# solar_tester.net
KiCad netlist of a schematic drawn in EAGLE
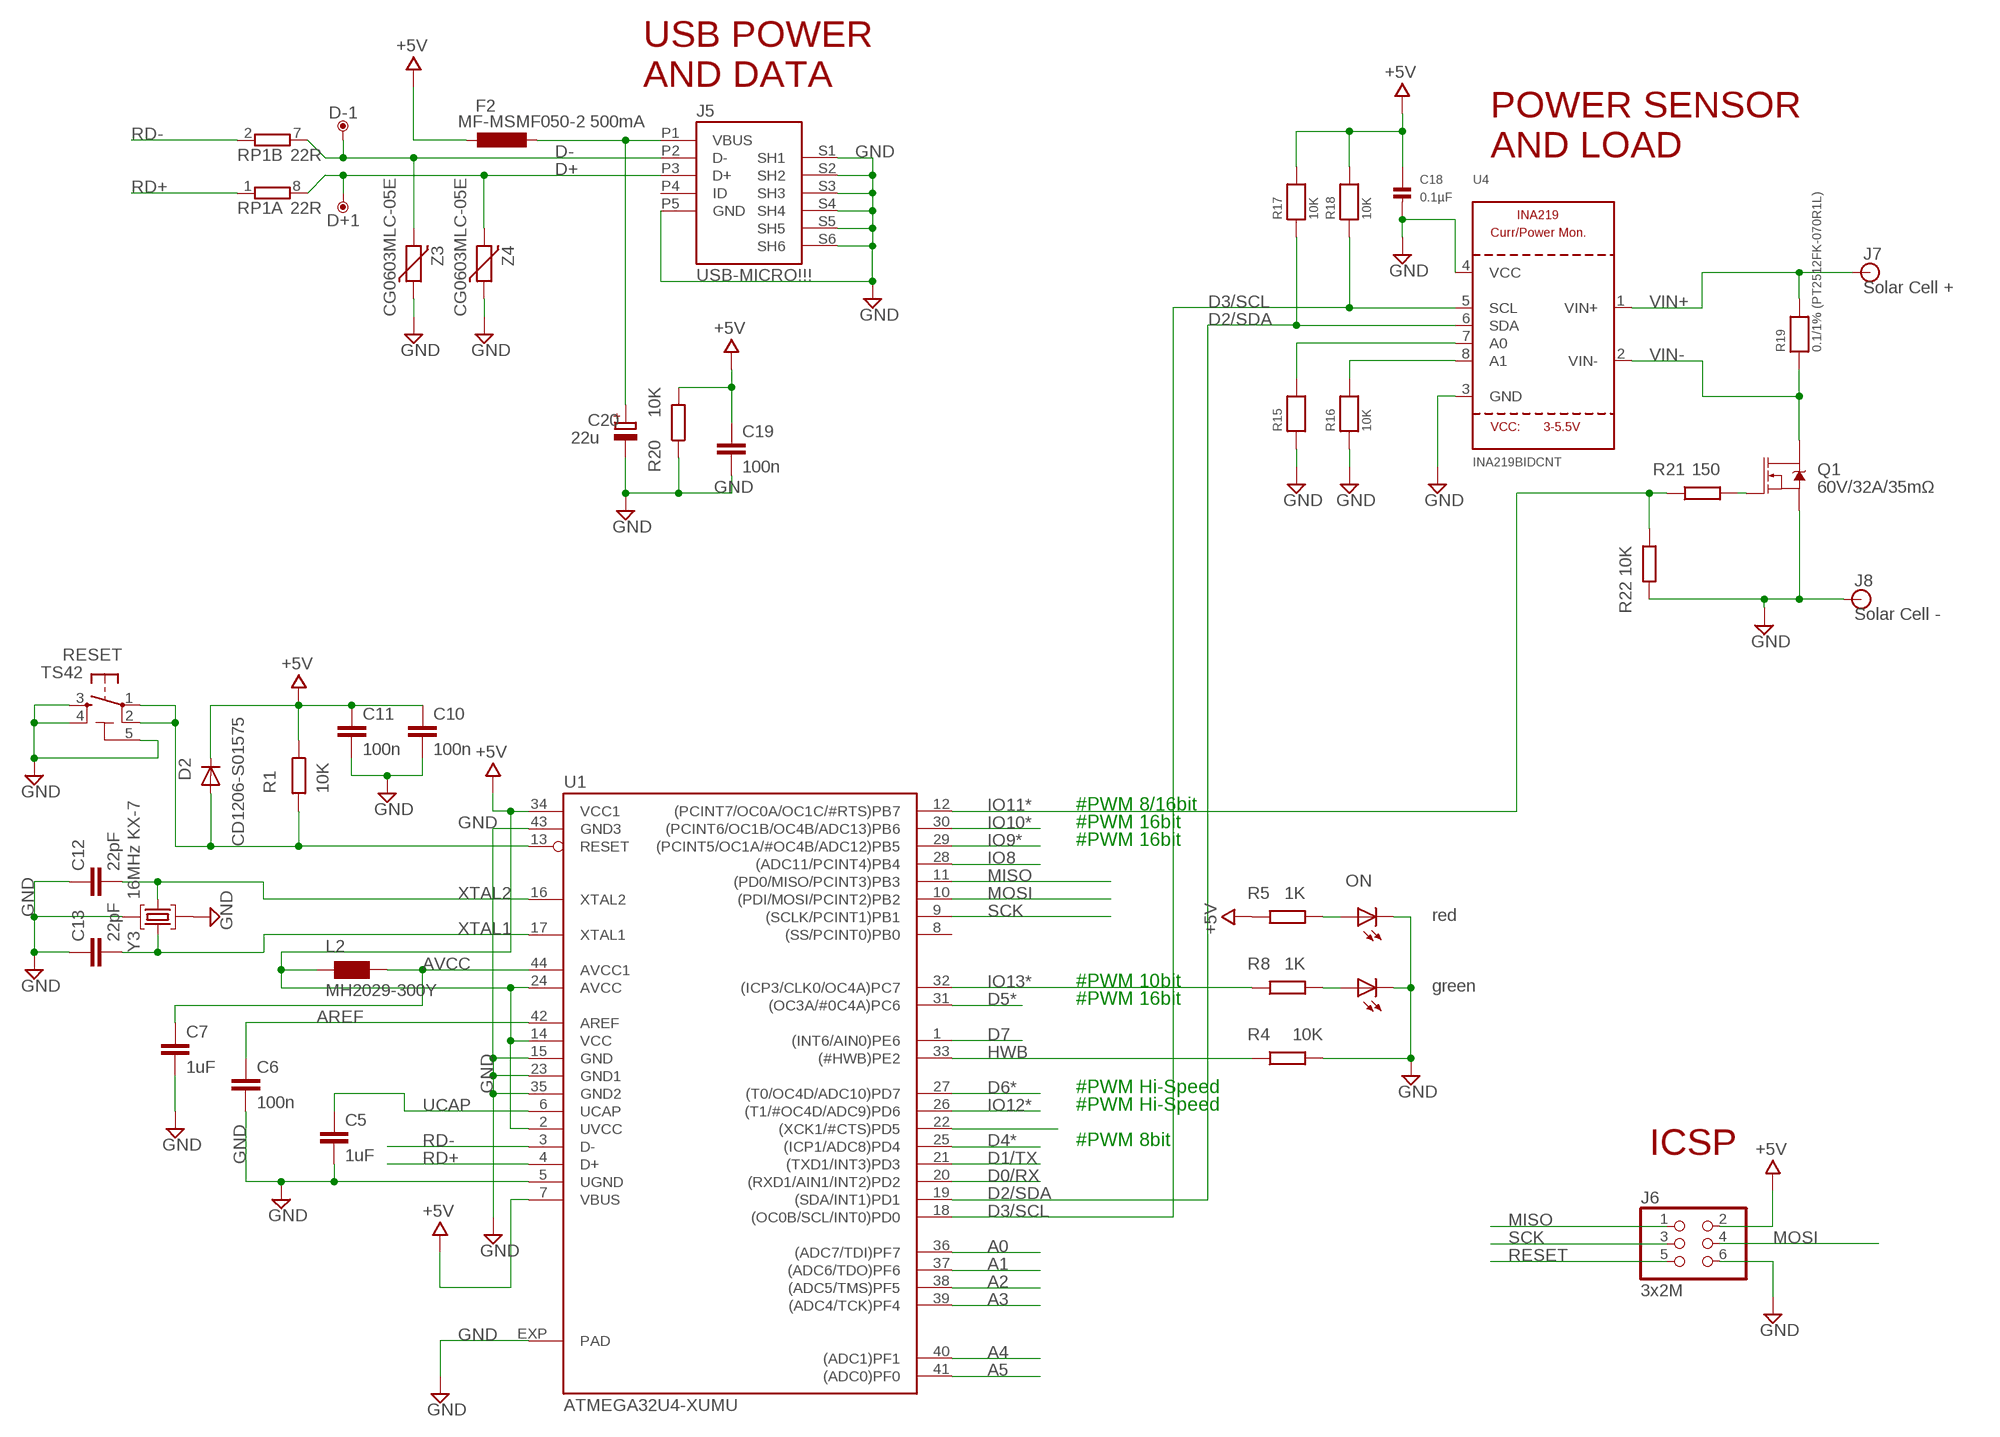
[diagram p0: schematic, sheet 1]

(export (version "E")
  (design (tool "Eeschema 10.0.6"))
  (components
    (comp (ref "C5")
      (value "1uF")
      (footprint "eagle-import:C0402")
      (libsource (lib "eagle-import") (part "C-EUC0402"))
    )
    (comp (ref "C6")
      (value "100n")
      (footprint "eagle-import:C0402")
      (libsource (lib "eagle-import") (part "C-EUC0402"))
    )
    (comp (ref "C7")
      (value "1uF")
      (footprint "eagle-import:C0402")
      (libsource (lib "eagle-import") (part "C-EUC0402"))
    )
    (comp (ref "C10")
      (value "100n")
      (footprint "eagle-import:C0402")
      (libsource (lib "eagle-import") (part "C-EUC0402"))
    )
    (comp (ref "C11")
      (value "100n")
      (footprint "eagle-import:C0402")
      (libsource (lib "eagle-import") (part "C-EUC0402"))
    )
    (comp (ref "C12")
      (value "22pF")
      (footprint "eagle-import:C0402")
      (libsource (lib "eagle-import") (part "C-EUC0402"))
    )
    (comp (ref "C13")
      (value "22pF")
      (footprint "eagle-import:C0402")
      (libsource (lib "eagle-import") (part "C-EUC0402"))
    )
    (comp (ref "C18")
      (value "0.1µF")
      (footprint "eagle-import:0805")
      (libsource (lib "eagle-import") (part "CAP_CERAMIC0805"))
    )
    (comp (ref "C19")
      (value "100n")
      (footprint "eagle-import:C0402")
      (libsource (lib "eagle-import") (part "C-EUC0402"))
    )
    (comp (ref "C20")
      (value "22u")
      (footprint "eagle-import:SMC_B")
      (libsource (lib "eagle-import") (part "CPOL-EUSMCB"))
    )
    (comp (ref "D+1")
      (value "DNP")
      (footprint "eagle-import:TP-1.00MM")
      (libsource (lib "eagle-import") (part "TPTP-1.00MM"))
    )
    (comp (ref "D-1")
      (value "DNP")
      (footprint "eagle-import:TP-1.00MM")
      (libsource (lib "eagle-import") (part "TPTP-1.00MM"))
    )
    (comp (ref "D2")
      (value "CD1206-S01575")
      (footprint "eagle-import:MINIMELF")
      (libsource (lib "eagle-import") (part "DIODE-MINIMELF"))
    )
    (comp (ref "F2")
      (value "MF-MSMF050-2 500mA")
      (footprint "eagle-import:L1812")
      (libsource (lib "eagle-import") (part "L-EUL1812"))
    )
    (comp (ref "J5")
      (value "USB-MICRO!!!")
      (footprint "eagle-import:CON2_USB_MICRO_B_AT")
      (libsource (lib "eagle-import") (part "MYCON2_USB-MINI-B"))
    )
    (comp (ref "J6")
      (value "3x2M")
      (footprint "eagle-import:2X03")
      (libsource (lib "eagle-import") (part "PINHD-2X3"))
    )
    (comp (ref "J7")
      (value "Solar Cell +")
      (footprint "eagle-import:BANANA_CONN")
      (libsource (lib "eagle-import") (part "BANANA_CONN"))
    )
    (comp (ref "J8")
      (value "Solar Cell -")
      (footprint "eagle-import:BANANA_CONN")
      (libsource (lib "eagle-import") (part "BANANA_CONN"))
    )
    (comp (ref "L")
      (value "green")
      (footprint "eagle-import:CHIPLED_0805")
      (libsource (lib "eagle-import") (part "LEDCHIPLED_0805"))
    )
    (comp (ref "L2")
      (value "MH2029-300Y")
      (footprint "eagle-import:0805")
      (libsource (lib "eagle-import") (part "WE-CBF_0805"))
    )
    (comp (ref "ON")
      (value "red")
      (footprint "eagle-import:CHIPLED_0805")
      (libsource (lib "eagle-import") (part "LEDCHIPLED_0805"))
    )
    (comp (ref "Q1")
      (value "60V/32A/35mΩ")
      (footprint "eagle-import:TO220V")
      (libsource (lib "eagle-import") (part "MOSFET-NCH-FQP30N06L"))
    )
    (comp (ref "R1")
      (value "10K")
      (footprint "eagle-import:R0402")
      (libsource (lib "eagle-import") (part "R-EU_R0402"))
    )
    (comp (ref "R4")
      (value "10K")
      (footprint "eagle-import:R0402")
      (libsource (lib "eagle-import") (part "R-EU_R0402"))
    )
    (comp (ref "R5")
      (value "1K")
      (footprint "eagle-import:R0402")
      (libsource (lib "eagle-import") (part "R-EU_R0402"))
    )
    (comp (ref "R8")
      (value "1K")
      (footprint "eagle-import:R0402")
      (libsource (lib "eagle-import") (part "R-EU_R0402"))
    )
    (comp (ref "R15")
      (value "10K")
      (footprint "eagle-import:0805")
      (libsource (lib "eagle-import") (part "RESISTOR0805"))
    )
    (comp (ref "R16")
      (value "10K")
      (footprint "eagle-import:0805")
      (libsource (lib "eagle-import") (part "RESISTOR0805"))
    )
    (comp (ref "R17")
      (value "10K")
      (footprint "eagle-import:0805")
      (libsource (lib "eagle-import") (part "RESISTOR0805"))
    )
    (comp (ref "R18")
      (value "10K")
      (footprint "eagle-import:0805")
      (libsource (lib "eagle-import") (part "RESISTOR0805"))
    )
    (comp (ref "R19")
      (value "0.1/1% (PT2512FK-070R1L)")
      (footprint "eagle-import:2512")
      (libsource (lib "eagle-import") (part "RESISTOR2512"))
    )
    (comp (ref "R20")
      (value "10K")
      (footprint "eagle-import:R0402")
      (libsource (lib "eagle-import") (part "R-EU_R0402"))
    )
    (comp (ref "R21")
      (value "150")
      (footprint "eagle-import:R0402")
      (libsource (lib "eagle-import") (part "R-EU_R0402"))
    )
    (comp (ref "R22")
      (value "10K")
      (footprint "eagle-import:R0402")
      (libsource (lib "eagle-import") (part "R-EU_R0402"))
    )
    (comp (ref "RESET")
      (value "TS42")
      (footprint "eagle-import:TS42")
      (libsource (lib "eagle-import") (part "TS42"))
    )
    (comp (ref "RP1")
      (value "22R")
      (footprint "eagle-import:CAY16")
      (libsource (lib "eagle-import") (part "4R-NCAY16"))
    )
    (comp (ref "U1")
      (value "ATMEGA32U4-XUMU")
      (footprint "eagle-import:QFN44ML7X7")
      (libsource (lib "eagle-import") (part "ATMEGA32U4-XUMU"))
    )
    (comp (ref "U4")
      (value "INA219BIDCNT")
      (footprint "eagle-import:SOT23-8")
      (libsource (lib "eagle-import") (part "INA219"))
    )
    (comp (ref "Y3")
      (value "16MHz KX-7")
      (footprint "eagle-import:CRYSTAL-3.2-2.5")
      (libsource (lib "eagle-import") (part "CRYSTAL-3.2-2.5"))
    )
    (comp (ref "Z3")
      (value "CG0603MLC-05E")
      (footprint "eagle-import:CT_CN0603")
      (libsource (lib "eagle-import") (part "VARISTORCN0603"))
    )
    (comp (ref "Z4")
      (value "CG0603MLC-05E")
      (footprint "eagle-import:CT_CN0603")
      (libsource (lib "eagle-import") (part "VARISTORCN0603"))
    )
  )
  (nets
    (net (code "1") (name "+5V") (class "Default")
      (node (ref "C10") (pin "1") (pinfunction "1_1") (pintype "passive"))
      (node (ref "C11") (pin "1") (pinfunction "1_1") (pintype "passive"))
      (node (ref "C18") (pin "1") (pinfunction "P$1_1") (pintype "passive"))
      (node (ref "C19") (pin "1") (pinfunction "1_1") (pintype "passive"))
      (node (ref "D2") (pin "C") (pinfunction "C_C") (pintype "passive"))
      (node (ref "F2") (pin "2") (pinfunction "2_2") (pintype "passive"))
      (node (ref "J6") (pin "2") (pinfunction "2_2") (pintype "passive"))
      (node (ref "L2") (pin "1") (pinfunction "1_1") (pintype "passive"))
      (node (ref "R1") (pin "1") (pinfunction "1_1") (pintype "passive"))
      (node (ref "R17") (pin "2") (pinfunction "2_2") (pintype "passive"))
      (node (ref "R18") (pin "2") (pinfunction "2_2") (pintype "passive"))
      (node (ref "R20") (pin "2") (pinfunction "2_2") (pintype "passive"))
      (node (ref "R5") (pin "1") (pinfunction "1_1") (pintype "passive"))
      (node (ref "U1") (pin "14") (pinfunction "VCC_14") (pintype "power_in"))
      (node (ref "U1") (pin "2") (pinfunction "UVCC_2") (pintype "power_in"))
      (node (ref "U1") (pin "24") (pinfunction "AVCC_24") (pintype "power_in"))
      (node (ref "U1") (pin "34") (pinfunction "VCC1_34") (pintype "power_in"))
      (node (ref "U1") (pin "7") (pinfunction "VBUS_7") (pintype "input"))
    )
    (net (code "2") (name "/A0") (class "Default")
      (node (ref "U1") (pin "36") (pinfunction "(ADC7/TDI)PF7_36") (pintype "bidirectional"))
    )
    (net (code "3") (name "/A1") (class "Default")
      (node (ref "U1") (pin "37") (pinfunction "(ADC6/TDO)PF6_37") (pintype "bidirectional"))
    )
    (net (code "4") (name "/A2") (class "Default")
      (node (ref "U1") (pin "38") (pinfunction "(ADC5/TMS)PF5_38") (pintype "bidirectional"))
    )
    (net (code "5") (name "/A3") (class "Default")
      (node (ref "U1") (pin "39") (pinfunction "(ADC4/TCK)PF4_39") (pintype "bidirectional"))
    )
    (net (code "6") (name "/A4") (class "Default")
      (node (ref "U1") (pin "40") (pinfunction "(ADC1)PF1_40") (pintype "bidirectional"))
    )
    (net (code "7") (name "/A5") (class "Default")
      (node (ref "U1") (pin "41") (pinfunction "(ADC0)PF0_41") (pintype "bidirectional"))
    )
    (net (code "8") (name "/AREF") (class "Default")
      (node (ref "C6") (pin "1") (pinfunction "1_1") (pintype "passive"))
      (node (ref "U1") (pin "42") (pinfunction "AREF_42") (pintype "power_in"))
    )
    (net (code "9") (name "/AVCC") (class "Default")
      (node (ref "C7") (pin "1") (pinfunction "1_1") (pintype "passive"))
      (node (ref "L2") (pin "2") (pinfunction "2_2") (pintype "passive"))
      (node (ref "U1") (pin "44") (pinfunction "AVCC1_44") (pintype "power_in"))
    )
    (net (code "10") (name "/D+") (class "Default")
      (node (ref "D+1") (pin "X") (pinfunction "P$1_X") (pintype "passive"))
      (node (ref "J5") (pin "P3") (pinfunction "D+_P3") (pintype "bidirectional"))
      (node (ref "RP1") (pin "8") (pinfunction "2_8") (pintype "passive"))
      (node (ref "Z4") (pin "2") (pinfunction "2_2") (pintype "passive"))
    )
    (net (code "11") (name "/D-") (class "Default")
      (node (ref "D-1") (pin "X") (pinfunction "P$1_X") (pintype "passive"))
      (node (ref "J5") (pin "P2") (pinfunction "D-_P2") (pintype "bidirectional"))
      (node (ref "RP1") (pin "7") (pinfunction "2_7") (pintype "passive"))
      (node (ref "Z3") (pin "2") (pinfunction "2_2") (pintype "passive"))
    )
    (net (code "12") (name "/D0{slash}RX") (class "Default")
      (node (ref "U1") (pin "20") (pinfunction "(RXD1/AIN1/INT2)PD2_20") (pintype "bidirectional"))
    )
    (net (code "13") (name "/D1{slash}TX") (class "Default")
      (node (ref "U1") (pin "21") (pinfunction "(TXD1/INT3)PD3_21") (pintype "bidirectional"))
    )
    (net (code "14") (name "/D2{slash}SDA") (class "Default")
      (node (ref "R17") (pin "1") (pinfunction "1_1") (pintype "passive"))
      (node (ref "U1") (pin "19") (pinfunction "(SDA/INT1)PD1_19") (pintype "bidirectional"))
      (node (ref "U4") (pin "6") (pinfunction "SDA_6") (pintype "bidirectional"))
    )
    (net (code "15") (name "/D3{slash}SCL") (class "Default")
      (node (ref "R18") (pin "1") (pinfunction "1_1") (pintype "passive"))
      (node (ref "U1") (pin "18") (pinfunction "(OC0B/SCL/INT0)PD0_18") (pintype "bidirectional"))
      (node (ref "U4") (pin "5") (pinfunction "SCL_5") (pintype "bidirectional"))
    )
    (net (code "16") (name "/D4*") (class "Default")
      (node (ref "U1") (pin "25") (pinfunction "(ICP1/ADC8)PD4_25") (pintype "bidirectional"))
    )
    (net (code "17") (name "/D5*") (class "Default")
      (node (ref "U1") (pin "31") (pinfunction "(OC3A/#0C4A)PC6_31") (pintype "bidirectional"))
    )
    (net (code "18") (name "/D6*") (class "Default")
      (node (ref "U1") (pin "27") (pinfunction "(T0/OC4D/ADC10)PD7_27") (pintype "bidirectional"))
    )
    (net (code "19") (name "/D7") (class "Default")
      (node (ref "U1") (pin "1") (pinfunction "(INT6/AIN0)PE6_1") (pintype "bidirectional"))
    )
    (net (code "20") (name "/HWB") (class "Default")
      (node (ref "R4") (pin "1") (pinfunction "1_1") (pintype "passive"))
      (node (ref "U1") (pin "33") (pinfunction "(#HWB)PE2_33") (pintype "bidirectional"))
    )
    (net (code "21") (name "/IO8") (class "Default")
      (node (ref "U1") (pin "28") (pinfunction "(ADC11/PCINT4)PB4_28") (pintype "bidirectional"))
    )
    (net (code "22") (name "/IO9*") (class "Default")
      (node (ref "U1") (pin "29") (pinfunction "(PCINT5/OC1A/#OC4B/ADC12)PB5_29") (pintype "bidirectional"))
    )
    (net (code "23") (name "/IO10*") (class "Default")
      (node (ref "U1") (pin "30") (pinfunction "(PCINT6/OC1B/OC4B/ADC13)PB6_30") (pintype "bidirectional"))
    )
    (net (code "24") (name "/IO11*") (class "Default")
      (node (ref "R21") (pin "1") (pinfunction "1_1") (pintype "passive"))
      (node (ref "R22") (pin "2") (pinfunction "2_2") (pintype "passive"))
      (node (ref "U1") (pin "12") (pinfunction "(PCINT7/OC0A/OC1C/#RTS)PB7_12") (pintype "bidirectional"))
    )
    (net (code "25") (name "/IO12*") (class "Default")
      (node (ref "U1") (pin "26") (pinfunction "(T1/#OC4D/ADC9)PD6_26") (pintype "bidirectional"))
    )
    (net (code "26") (name "/IO13*") (class "Default")
      (node (ref "R8") (pin "1") (pinfunction "1_1") (pintype "passive"))
      (node (ref "U1") (pin "32") (pinfunction "(ICP3/CLK0/OC4A)PC7_32") (pintype "bidirectional"))
    )
    (net (code "27") (name "/MISO") (class "Default")
      (node (ref "J6") (pin "1") (pinfunction "1_1") (pintype "passive"))
      (node (ref "U1") (pin "11") (pinfunction "(PD0/MISO/PCINT3)PB3_11") (pintype "bidirectional"))
    )
    (net (code "28") (name "/MOSI") (class "Default")
      (node (ref "J6") (pin "4") (pinfunction "4_4") (pintype "passive"))
      (node (ref "U1") (pin "10") (pinfunction "(PDI/MOSI/PCINT2)PB2_10") (pintype "bidirectional"))
    )
    (net (code "29") (name "/RD+") (class "Default")
      (node (ref "RP1") (pin "1") (pinfunction "1_1") (pintype "passive"))
      (node (ref "U1") (pin "4") (pinfunction "D+_4") (pintype "bidirectional"))
    )
    (net (code "30") (name "/RD-") (class "Default")
      (node (ref "RP1") (pin "2") (pinfunction "1_2") (pintype "passive"))
      (node (ref "U1") (pin "3") (pinfunction "D-_3") (pintype "bidirectional"))
    )
    (net (code "31") (name "/RESET") (class "Default")
      (node (ref "J6") (pin "5") (pinfunction "5_5") (pintype "passive"))
    )
    (net (code "32") (name "/SCK") (class "Default")
      (node (ref "J6") (pin "3") (pinfunction "3_3") (pintype "passive"))
      (node (ref "U1") (pin "9") (pinfunction "(SCLK/PCINT1)PB1_9") (pintype "bidirectional"))
    )
    (net (code "33") (name "/UCAP") (class "Default")
      (node (ref "C5") (pin "1") (pinfunction "1_1") (pintype "passive"))
      (node (ref "U1") (pin "6") (pinfunction "UCAP_6") (pintype "passive"))
    )
    (net (code "34") (name "/VIN+") (class "Default")
      (node (ref "J7") (pin "P$1") (pinfunction "1_P$1") (pintype "passive"))
      (node (ref "R19") (pin "2") (pinfunction "2_2") (pintype "passive"))
      (node (ref "U4") (pin "1") (pinfunction "VIN+_1") (pintype "bidirectional"))
    )
    (net (code "35") (name "/VIN-") (class "Default")
      (node (ref "Q1") (pin "2") (pinfunction "D_2") (pintype "bidirectional"))
      (node (ref "R19") (pin "1") (pinfunction "1_1") (pintype "passive"))
      (node (ref "U4") (pin "2") (pinfunction "VIN-_2") (pintype "bidirectional"))
    )
    (net (code "36") (name "/XTAL1") (class "Default")
      (node (ref "C13") (pin "2") (pinfunction "2_2") (pintype "passive"))
      (node (ref "U1") (pin "17") (pinfunction "XTAL1_17") (pintype "bidirectional"))
      (node (ref "Y3") (pin "3") (pinfunction "C2_3") (pintype "passive"))
    )
    (net (code "37") (name "/XTAL2") (class "Default")
      (node (ref "C12") (pin "2") (pinfunction "2_2") (pintype "passive"))
      (node (ref "U1") (pin "16") (pinfunction "XTAL2_16") (pintype "bidirectional"))
      (node (ref "Y3") (pin "1") (pinfunction "C1_1") (pintype "passive"))
    )
    (net (code "38") (name "GND") (class "Default")
      (node (ref "C10") (pin "2") (pinfunction "2_2") (pintype "passive"))
      (node (ref "C11") (pin "2") (pinfunction "2_2") (pintype "passive"))
      (node (ref "C12") (pin "1") (pinfunction "1_1") (pintype "passive"))
      (node (ref "C13") (pin "1") (pinfunction "1_1") (pintype "passive"))
      (node (ref "C18") (pin "2") (pinfunction "P$2_2") (pintype "passive"))
      (node (ref "C19") (pin "2") (pinfunction "2_2") (pintype "passive"))
      (node (ref "C20") (pin "-") (pinfunction "-_-") (pintype "passive"))
      (node (ref "C5") (pin "2") (pinfunction "2_2") (pintype "passive"))
      (node (ref "C6") (pin "2") (pinfunction "2_2") (pintype "passive"))
      (node (ref "C7") (pin "2") (pinfunction "2_2") (pintype "passive"))
      (node (ref "J5") (pin "P5") (pinfunction "GND_P5") (pintype "passive"))
      (node (ref "J5") (pin "S1") (pinfunction "SH1_S1") (pintype "passive"))
      (node (ref "J5") (pin "S2") (pinfunction "SH2_S2") (pintype "passive"))
      (node (ref "J5") (pin "S3") (pinfunction "SH3_S3") (pintype "passive"))
      (node (ref "J5") (pin "S4") (pinfunction "SH4_S4") (pintype "passive"))
      (node (ref "J5") (pin "S5") (pinfunction "SH5_S5") (pintype "passive"))
      (node (ref "J5") (pin "S6") (pinfunction "SH6_S6") (pintype "passive"))
      (node (ref "J6") (pin "6") (pinfunction "6_6") (pintype "passive"))
      (node (ref "J8") (pin "P$1") (pinfunction "1_P$1") (pintype "passive"))
      (node (ref "L") (pin "C") (pinfunction "C_C") (pintype "passive"))
      (node (ref "ON") (pin "C") (pinfunction "C_C") (pintype "passive"))
      (node (ref "Q1") (pin "3") (pinfunction "S_3") (pintype "bidirectional"))
      (node (ref "R15") (pin "1") (pinfunction "1_1") (pintype "passive"))
      (node (ref "R16") (pin "1") (pinfunction "1_1") (pintype "passive"))
      (node (ref "R20") (pin "1") (pinfunction "1_1") (pintype "passive"))
      (node (ref "R22") (pin "1") (pinfunction "1_1") (pintype "passive"))
      (node (ref "R4") (pin "2") (pinfunction "2_2") (pintype "passive"))
      (node (ref "RESET") (pin "3") (pinfunction "3_3") (pintype "passive"))
      (node (ref "RESET") (pin "4") (pinfunction "4_4") (pintype "passive"))
      (node (ref "RESET") (pin "5") (pinfunction "5-GND_5") (pintype "power_in"))
      (node (ref "U1") (pin "15") (pinfunction "GND_15") (pintype "power_in"))
      (node (ref "U1") (pin "23") (pinfunction "GND1_23") (pintype "power_in"))
      (node (ref "U1") (pin "35") (pinfunction "GND2_35") (pintype "power_in"))
      (node (ref "U1") (pin "43") (pinfunction "GND3_43") (pintype "power_in"))
      (node (ref "U1") (pin "5") (pinfunction "UGND_5") (pintype "power_in"))
      (node (ref "U1") (pin "EXP") (pinfunction "PAD_EXP") (pintype "power_in"))
      (node (ref "U4") (pin "3") (pinfunction "GND_3") (pintype "bidirectional"))
      (node (ref "U4") (pin "4") (pinfunction "VCC_4") (pintype "bidirectional"))
      (node (ref "Y3") (pin "2") (pinfunction "GND_2") (pintype "passive"))
      (node (ref "Y3") (pin "4") (pinfunction "GND_4") (pintype "passive"))
      (node (ref "Z3") (pin "1") (pinfunction "1_1") (pintype "passive"))
      (node (ref "Z4") (pin "1") (pinfunction "1_1") (pintype "passive"))
    )
    (net (code "39") (name "Net-(J5-VBUS)") (class "Default")
      (node (ref "C20") (pin "+") (pinfunction "+_+") (pintype "passive"))
      (node (ref "F2") (pin "1") (pinfunction "1_1") (pintype "passive"))
      (node (ref "J5") (pin "P1") (pinfunction "VBUS_P1") (pintype "power_in"))
    )
    (net (code "40") (name "Net-(L-PadA)") (class "Default")
      (node (ref "L") (pin "A") (pinfunction "A_A") (pintype "passive"))
      (node (ref "R8") (pin "2") (pinfunction "2_2") (pintype "passive"))
    )
    (net (code "41") (name "Net-(ON-PadA)") (class "Default")
      (node (ref "ON") (pin "A") (pinfunction "A_A") (pintype "passive"))
      (node (ref "R5") (pin "2") (pinfunction "2_2") (pintype "passive"))
    )
    (net (code "42") (name "Net-(Q1-G)") (class "Default")
      (node (ref "Q1") (pin "1") (pinfunction "G_1") (pintype "bidirectional"))
      (node (ref "R21") (pin "2") (pinfunction "2_2") (pintype "passive"))
    )
    (net (code "43") (name "Net-(U1-RESET)") (class "Default")
      (node (ref "D2") (pin "A") (pinfunction "A_A") (pintype "passive"))
      (node (ref "R1") (pin "2") (pinfunction "2_2") (pintype "passive"))
      (node (ref "RESET") (pin "1") (pinfunction "1_1") (pintype "passive"))
      (node (ref "RESET") (pin "2") (pinfunction "2_2") (pintype "passive"))
      (node (ref "U1") (pin "13") (pinfunction "RESET_13") (pintype "input"))
    )
    (net (code "44") (name "Net-(U4-A0)") (class "Default")
      (node (ref "R15") (pin "2") (pinfunction "2_2") (pintype "passive"))
      (node (ref "U4") (pin "7") (pinfunction "A0_7") (pintype "bidirectional"))
    )
    (net (code "45") (name "Net-(U4-A1)") (class "Default")
      (node (ref "R16") (pin "2") (pinfunction "2_2") (pintype "passive"))
      (node (ref "U4") (pin "8") (pinfunction "A1_8") (pintype "bidirectional"))
    )
    (net (code "46") (name "unconnected-(J5-ID-PadP4)") (class "Default")
      (node (ref "J5") (pin "P4") (pinfunction "ID_P4") (pintype "bidirectional"))
    )
    (net (code "47") (name "unconnected-(U1-(SS{slash}PCINT0)PB0-Pad8)") (class "Default")
      (node (ref "U1") (pin "8") (pinfunction "(SS/PCINT0)PB0_8") (pintype "bidirectional"))
    )
    (net (code "48") (name "unconnected-(U1-(XCK1{slash}#CTS)PD5-Pad22)") (class "Default")
      (node (ref "U1") (pin "22") (pinfunction "(XCK1/#CTS)PD5_22") (pintype "bidirectional"))
    )
  )
)
